# ESP32.net
KiCad netlist of a schematic drawn in Altium Designer
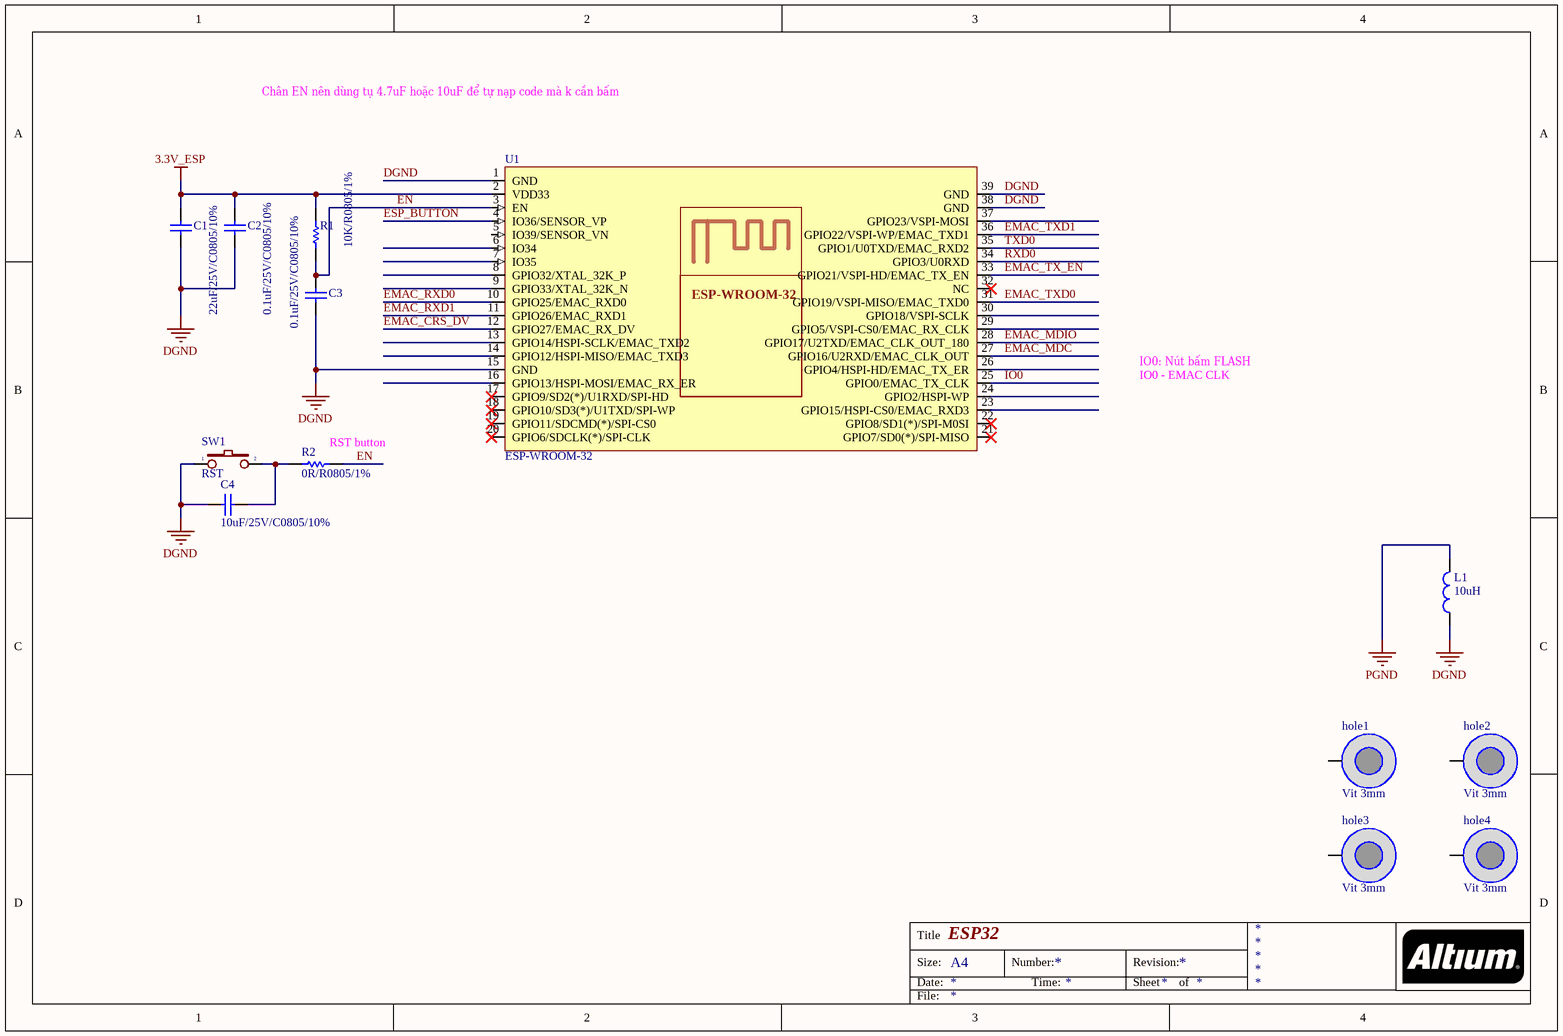
[diagram p0: ESP32.SchDoc]

(export (version "E")
  (design (tool "Eeschema 10.0.6"))
  (components
    (comp (ref "C1")
      (value "22uF/25V/C0805/10%")
      (footprint "CAP_CERA_C2012(CC0805INCH)")
      (description "22µF ±20% 25V Ceramic Capacitor X5R 0805 (2012 Metric)")
      (fields (field (name "MANUFACTURER") "Tariff Applied"))
      (libsource (lib "GSHT_181013") (part "0.1uF/50V/C0603/10%"))
    )
    (comp (ref "C2")
      (value "0.1uF/25V/C0805/10%")
      (footprint "CAP_CERA_C2012(CC0805INCH)")
      (description "0.1µF ±10% 25V Ceramic Capacitor X7R 0805 (2012 Metric)")
      (libsource (lib "GSHT_181013") (part "0.1uF/50V/C0603/10%"))
    )
    (comp (ref "C3")
      (value "0.1uF/25V/C0805/10%")
      (footprint "CAP_CERA_C2012(CC0805INCH)")
      (description "0.1µF ±10% 25V Ceramic Capacitor X7R 0805 (2012 Metric)")
      (libsource (lib "GSHT_181013") (part "0.1uF/50V/C0603/10%"))
    )
    (comp (ref "C4")
      (value "10uF/25V/C0805/10%")
      (footprint "CAP_CERA_C2012(CC0805INCH)")
      (description "0.1µF ±10% 25V Ceramic Capacitor X7R 0805 (2012 Metric)")
      (libsource (lib "GSHT_181013") (part "0.1uF/50V/C0603/10%"))
    )
    (comp (ref "hole1") (value "Vit 3mm") (footprint "Screw 3.0") (libsource (lib "lpson") (part "Vit 3mm")))
    (comp (ref "hole2") (value "Vit 3mm") (footprint "Screw 3.0") (libsource (lib "lpson") (part "Vit 3mm")))
    (comp (ref "hole3") (value "Vit 3mm") (footprint "Screw 3.0") (libsource (lib "lpson") (part "Vit 3mm")))
    (comp (ref "hole4") (value "Vit 3mm") (footprint "Screw 3.0") (libsource (lib "lpson") (part "Vit 3mm")))
    (comp (ref "L1")
      (value "10uH")
      (footprint "L/0.4")
      (description "Inductor")
      (libsource (lib "lpson") (part "L1"))
    )
    (comp (ref "R1")
      (value "10K/R0805/1%")
      (footprint "Res 0805 SMD")
      (description "10 kOhms ±1% 0.125W, 1/8W Chip Resistor 0805 (2012 Metric) Thick Film")
      (libsource (lib "GSHT_181013") (part "200K/R0603/1%"))
    )
    (comp (ref "R2")
      (value "0R/R0805/1%")
      (footprint "Res 0805 SMD")
      (description "0 Ohms Jumper 0.125W, 1/8W Chip Resistor 0805 (2012 Metric) Automotive AEC-Q200 Thick Film")
      (libsource (lib "GSHT_181013") (part "200K/R0603/1%"))
    )
    (comp (ref "SW1")
      (value "RST")
      (footprint "Button 3x4mm")
      (description "SWITCH TACTILE SPST-NO 0.05A 12V")
      (libsource (lib "lpson") (part "SW2"))
    )
    (comp (ref "U1")
      (value "ESP-WROOM-32")
      (footprint "ESP32 WROOM")
      (description "ESP-WROOM-32 (8MB), WIFI MODULE 64 MBITS SPI FLASH")
      (libsource (lib "lpson") (part "ESP-WROOM-32"))
    )
  )
  (nets
    (net (code "1") (name "/EMAC_CRS_DV") (class "Default")
      (node (ref "U1") (pin "12") (pinfunction "GPIO27/EMAC_RX_DV_12") (pintype "passive"))
    )
    (net (code "2") (name "/EMAC_MDC") (class "Default")
      (node (ref "U1") (pin "27") (pinfunction "GPIO16/U2RXD/EMAC_CLK_OUT_27") (pintype "passive"))
    )
    (net (code "3") (name "/EMAC_MDIO") (class "Default")
      (node (ref "U1") (pin "28") (pinfunction "GPIO17/U2TXD/EMAC_CLK_OUT_180_28") (pintype "passive"))
    )
    (net (code "4") (name "/EMAC_RXD0") (class "Default")
      (node (ref "U1") (pin "10") (pinfunction "GPIO25/EMAC_RXD0_10") (pintype "passive"))
    )
    (net (code "5") (name "/EMAC_RXD1") (class "Default")
      (node (ref "U1") (pin "11") (pinfunction "GPIO26/EMAC_RXD1_11") (pintype "passive"))
    )
    (net (code "6") (name "/EMAC_TXD0") (class "Default")
      (node (ref "U1") (pin "31") (pinfunction "GPIO19/VSPI-MISO/EMAC_TXD0_31") (pintype "passive"))
    )
    (net (code "7") (name "/EMAC_TXD1") (class "Default")
      (node (ref "U1") (pin "36") (pinfunction "GPIO22/VSPI-WP/EMAC_TXD1_36") (pintype "passive"))
    )
    (net (code "8") (name "/EMAC_TX_EN") (class "Default")
      (node (ref "U1") (pin "33") (pinfunction "GPIO21/VSPI-HD/EMAC_TX_EN_33") (pintype "passive"))
    )
    (net (code "9") (name "/EN") (class "Default")
      (node (ref "C3") (pin "2") (pinfunction "2_2") (pintype "passive"))
      (node (ref "R1") (pin "2") (pinfunction "2_2") (pintype "passive"))
      (node (ref "R2") (pin "2") (pinfunction "2_2") (pintype "passive"))
      (node (ref "U1") (pin "3") (pinfunction "EN_3") (pintype "input"))
    )
    (net (code "10") (name "/ESP_BUTTON") (class "Default")
      (node (ref "U1") (pin "4") (pinfunction "IO36/SENSOR_VP_4") (pintype "input"))
    )
    (net (code "11") (name "/IO0") (class "Default")
      (node (ref "U1") (pin "25") (pinfunction "GPIO0/EMAC_TX_CLK_25") (pintype "passive"))
    )
    (net (code "12") (name "/RXD0") (class "Default")
      (node (ref "U1") (pin "34") (pinfunction "GPIO3/U0RXD_34") (pintype "passive"))
    )
    (net (code "13") (name "/TXD0") (class "Default")
      (node (ref "U1") (pin "35") (pinfunction "GPIO1/U0TXD/EMAC_RXD2_35") (pintype "passive"))
    )
    (net (code "14") (name "3.3V_ESP") (class "Default")
      (node (ref "C1") (pin "2") (pinfunction "2_2") (pintype "passive"))
      (node (ref "C2") (pin "2") (pinfunction "2_2") (pintype "passive"))
      (node (ref "R1") (pin "1") (pinfunction "1_1") (pintype "passive"))
      (node (ref "U1") (pin "2") (pinfunction "VDD33_2") (pintype "passive"))
    )
    (net (code "15") (name "DGND") (class "Default")
      (node (ref "C1") (pin "1") (pinfunction "1_1") (pintype "passive"))
      (node (ref "C2") (pin "1") (pinfunction "1_1") (pintype "passive"))
      (node (ref "C3") (pin "1") (pinfunction "1_1") (pintype "passive"))
      (node (ref "C4") (pin "2") (pinfunction "2_2") (pintype "passive"))
      (node (ref "L1") (pin "1") (pinfunction "1_1") (pintype "passive"))
      (node (ref "SW1") (pin "1") (pinfunction "1_1") (pintype "passive"))
      (node (ref "U1") (pin "1") (pinfunction "GND_1") (pintype "passive"))
      (node (ref "U1") (pin "15") (pinfunction "GND_15") (pintype "passive"))
      (node (ref "U1") (pin "38") (pinfunction "GND_38") (pintype "passive"))
      (node (ref "U1") (pin "39") (pinfunction "GND_39") (pintype "passive"))
    )
    (net (code "16") (name "Net-(C4-Pad1)") (class "Default")
      (node (ref "C4") (pin "1") (pinfunction "1_1") (pintype "passive"))
      (node (ref "R2") (pin "1") (pinfunction "1_1") (pintype "passive"))
      (node (ref "SW1") (pin "2") (pinfunction "2_2") (pintype "passive"))
    )
    (net (code "17") (name "PGND") (class "Default")
      (node (ref "L1") (pin "2") (pinfunction "2_2") (pintype "passive"))
    )
    (net (code "18") (name "unconnected-(U1-GPIO2{slash}HSPI-WP-Pad24)") (class "Default")
      (node (ref "U1") (pin "24") (pinfunction "GPIO2/HSPI-WP_24") (pintype "passive"))
    )
    (net (code "19") (name "unconnected-(U1-GPIO4{slash}HSPI-HD{slash}EMAC_TX_ER-Pad26)") (class "Default")
      (node (ref "U1") (pin "26") (pinfunction "GPIO4/HSPI-HD/EMAC_TX_ER_26") (pintype "passive"))
    )
    (net (code "20") (name "unconnected-(U1-GPIO5{slash}VSPI-CS0{slash}EMAC_RX_CLK-Pad29)") (class "Default")
      (node (ref "U1") (pin "29") (pinfunction "GPIO5/VSPI-CS0/EMAC_RX_CLK_29") (pintype "passive"))
    )
    (net (code "21") (name "unconnected-(U1-GPIO6{slash}SDCLK(*){slash}SPI-CLK-Pad20)") (class "Default")
      (node (ref "U1") (pin "20") (pinfunction "GPIO6/SDCLK(*)/SPI-CLK_20") (pintype "passive+no_connect"))
    )
    (net (code "22") (name "unconnected-(U1-GPIO7{slash}SD0(*){slash}SPI-MISO-Pad21)") (class "Default")
      (node (ref "U1") (pin "21") (pinfunction "GPIO7/SD0(*)/SPI-MISO_21") (pintype "passive+no_connect"))
    )
    (net (code "23") (name "unconnected-(U1-GPIO8{slash}SD1(*){slash}SPI-M0SI-Pad22)") (class "Default")
      (node (ref "U1") (pin "22") (pinfunction "GPIO8/SD1(*)/SPI-M0SI_22") (pintype "passive+no_connect"))
    )
    (net (code "24") (name "unconnected-(U1-GPIO9{slash}SD2(*){slash}U1RXD{slash}SPI-HD-Pad17)") (class "Default")
      (node (ref "U1") (pin "17") (pinfunction "GPIO9/SD2(*)/U1RXD/SPI-HD_17") (pintype "passive+no_connect"))
    )
    (net (code "25") (name "unconnected-(U1-GPIO10{slash}SD3(*){slash}U1TXD{slash}SPI-WP-Pad18)") (class "Default")
      (node (ref "U1") (pin "18") (pinfunction "GPIO10/SD3(*)/U1TXD/SPI-WP_18") (pintype "passive+no_connect"))
    )
    (net (code "26") (name "unconnected-(U1-GPIO11{slash}SDCMD(*){slash}SPI-CS0-Pad19)") (class "Default")
      (node (ref "U1") (pin "19") (pinfunction "GPIO11/SDCMD(*)/SPI-CS0_19") (pintype "passive+no_connect"))
    )
    (net (code "27") (name "unconnected-(U1-GPIO12{slash}HSPI-MISO{slash}EMAC_TXD3-Pad14)") (class "Default")
      (node (ref "U1") (pin "14") (pinfunction "GPIO12/HSPI-MISO/EMAC_TXD3_14") (pintype "passive"))
    )
    (net (code "28") (name "unconnected-(U1-GPIO13{slash}HSPI-MOSI{slash}EMAC_RX_ER-Pad16)") (class "Default")
      (node (ref "U1") (pin "16") (pinfunction "GPIO13/HSPI-MOSI/EMAC_RX_ER_16") (pintype "passive"))
    )
    (net (code "29") (name "unconnected-(U1-GPIO14{slash}HSPI-SCLK{slash}EMAC_TXD2-Pad13)") (class "Default")
      (node (ref "U1") (pin "13") (pinfunction "GPIO14/HSPI-SCLK/EMAC_TXD2_13") (pintype "passive"))
    )
    (net (code "30") (name "unconnected-(U1-GPIO15{slash}HSPI-CS0{slash}EMAC_RXD3-Pad23)") (class "Default")
      (node (ref "U1") (pin "23") (pinfunction "GPIO15/HSPI-CS0/EMAC_RXD3_23") (pintype "passive"))
    )
    (net (code "31") (name "unconnected-(U1-GPIO18{slash}VSPI-SCLK-Pad30)") (class "Default")
      (node (ref "U1") (pin "30") (pinfunction "GPIO18/VSPI-SCLK_30") (pintype "passive"))
    )
    (net (code "32") (name "unconnected-(U1-GPIO23{slash}VSPI-MOSI-Pad37)") (class "Default")
      (node (ref "U1") (pin "37") (pinfunction "GPIO23/VSPI-MOSI_37") (pintype "passive"))
    )
    (net (code "33") (name "unconnected-(U1-GPIO32{slash}XTAL_32K_P-Pad8)") (class "Default")
      (node (ref "U1") (pin "8") (pinfunction "GPIO32/XTAL_32K_P_8") (pintype "passive"))
    )
    (net (code "34") (name "unconnected-(U1-GPIO33{slash}XTAL_32K_N-Pad9)") (class "Default")
      (node (ref "U1") (pin "9") (pinfunction "GPIO33/XTAL_32K_N_9") (pintype "passive"))
    )
    (net (code "35") (name "unconnected-(U1-IO34-Pad6)") (class "Default")
      (node (ref "U1") (pin "6") (pinfunction "IO34_6") (pintype "input"))
    )
    (net (code "36") (name "unconnected-(U1-IO35-Pad7)") (class "Default")
      (node (ref "U1") (pin "7") (pinfunction "IO35_7") (pintype "input"))
    )
    (net (code "37") (name "unconnected-(U1-IO39{slash}SENSOR_VN-Pad5)") (class "Default")
      (node (ref "U1") (pin "5") (pinfunction "IO39/SENSOR_VN_5") (pintype "input"))
    )
    (net (code "38") (name "unconnected-(U1-NC-Pad32)") (class "Default")
      (node (ref "U1") (pin "32") (pinfunction "NC_32") (pintype "passive+no_connect"))
    )
    (net (code "39") (name "unconnected-(hole1-hole-Pad1)") (class "Default")
      (node (ref "hole1") (pin "1") (pinfunction "hole_1") (pintype "passive"))
    )
    (net (code "40") (name "unconnected-(hole2-hole-Pad1)") (class "Default")
      (node (ref "hole2") (pin "1") (pinfunction "hole_1") (pintype "passive"))
    )
    (net (code "41") (name "unconnected-(hole3-hole-Pad1)") (class "Default")
      (node (ref "hole3") (pin "1") (pinfunction "hole_1") (pintype "passive"))
    )
    (net (code "42") (name "unconnected-(hole4-hole-Pad1)") (class "Default")
      (node (ref "hole4") (pin "1") (pinfunction "hole_1") (pintype "passive"))
    )
  )
)
